# SENSOR_Board.net
KiCad netlist of a schematic drawn in Altium Designer
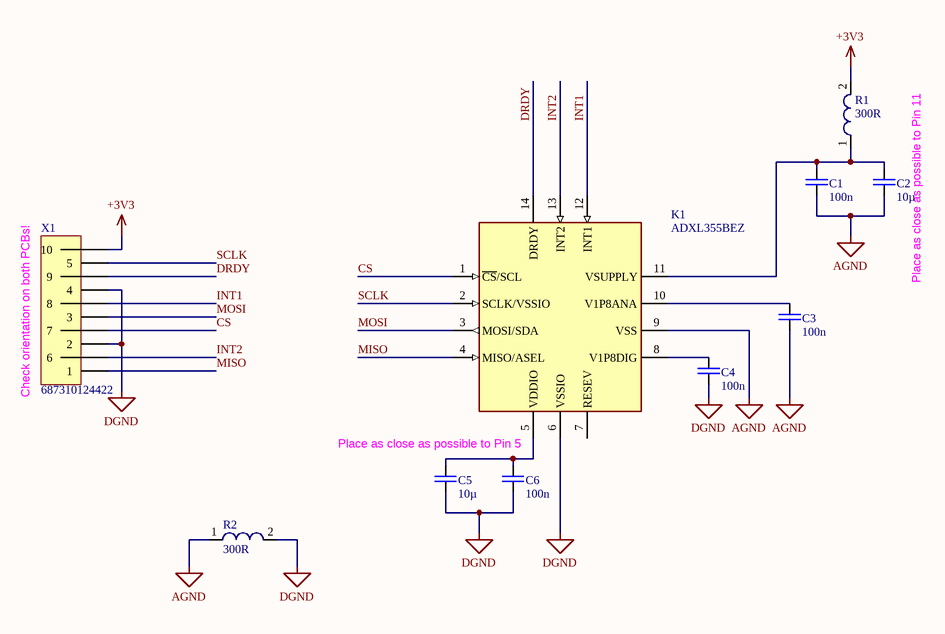
[diagram p0: SENSOR_Board.SchDoc]

(export (version "E")
  (design (tool "Eeschema 10.0.6"))
  (components
    (comp (ref "C1")
      (value "100n")
      (footprint "CAPC1608X08N")
      (description "100n, 0603, X7R, 10%, 50 V")
      (fields (field (name "MANUFACTURER") "Kemet") (field (name "TOLERANCE") "10%"))
      (libsource (lib "Capacitors") (part "C0603C104K5RACTU"))
    )
    (comp (ref "C2")
      (value "10µ")
      (footprint "CAPC2012X14N")
      (description "10µ, 0805, X5R, 10%, 16 V")
      (fields (field (name "MANUFACTURER") "Kemet") (field (name "TOLERANCE") "10%"))
      (libsource (lib "Capacitors") (part "C0805C106K4PACTU"))
    )
    (comp (ref "C3")
      (value "100n")
      (footprint "CAPC1608X08N")
      (description "100n, 0603, X7R, 10%, 50 V")
      (fields (field (name "MANUFACTURER") "Kemet") (field (name "TOLERANCE") "10%"))
      (libsource (lib "Capacitors") (part "C0603C104K5RACTU"))
    )
    (comp (ref "C4")
      (value "100n")
      (footprint "CAPC1608X08N")
      (description "100n, 0603, X7R, 10%, 50 V")
      (fields (field (name "MANUFACTURER") "Kemet") (field (name "TOLERANCE") "10%"))
      (libsource (lib "Capacitors") (part "C0603C104K5RACTU"))
    )
    (comp (ref "C5")
      (value "10µ")
      (footprint "CAPC2012X14N")
      (description "10µ, 0805, X5R, 10%, 16 V")
      (fields (field (name "MANUFACTURER") "Kemet") (field (name "TOLERANCE") "10%"))
      (libsource (lib "Capacitors") (part "C0805C106K4PACTU"))
    )
    (comp (ref "C6")
      (value "100n")
      (footprint "CAPC1608X08N")
      (description "100n, 0603, X7R, 10%, 50 V")
      (fields (field (name "MANUFACTURER") "Kemet") (field (name "TOLERANCE") "10%"))
      (libsource (lib "Capacitors") (part "C0603C104K5RACTU"))
    )
    (comp (ref "K1")
      (value "ADXL355BEZ")
      (footprint "FP-E-14-1-MFG")
      (description "ACCELEROMETER2-4-8GDIGTL14QFN")
      (fields (field (name "MANUFACTURER") "Analog Devices"))
      (libsource (lib "Sensors_MIBE") (part "ADXL355BEZ"))
    )
    (comp (ref "R1")
      (value "300R")
      (footprint "0603 (WE-CBF)")
      (description "300R / 100 MHz, 2 A, 0R15, WE-CBF")
      (fields
        (field (name "MANUFACTURER") "Wurth Electronics")
        (field (name "MANUFACTURER PART NUMBER") "742792641")
      )
      (libsource (lib "Inductors_MIBE") (part "742792641"))
    )
    (comp (ref "R2")
      (value "300R")
      (footprint "0603 (WE-CBF)")
      (description "300R / 100 MHz, 2 A, 0R15, WE-CBF")
      (fields
        (field (name "MANUFACTURER") "Wurth Electronics")
        (field (name "MANUFACTURER PART NUMBER") "742792641")
      )
      (libsource (lib "Inductors_MIBE") (part "742792641"))
    )
    (comp (ref "X1")
      (value "687310124422")
      (footprint "687310124422")
      (description "Ffc / Fpc Board Connector, Vertical, Surface Mount, Receptacle, 10, 0.5 Mm Rohs Compliant: Yes")
      (fields (field (name "MANUFACTURER") "Wurth Electronics"))
      (libsource (lib "Connectors_MIBE") (part "687310124422"))
    )
  )
  (nets
    (net (code "1") (name "+3V3") (class "Default")
      (node (ref "R1") (pin "2") (pinfunction "2_2") (pintype "passive"))
      (node (ref "X1") (pin "10") (pinfunction "10_10") (pintype "passive"))
    )
    (net (code "2") (name "/CS") (class "Default")
      (node (ref "K1") (pin "1") (pinfunction "~{CS}/SCL_1") (pintype "input"))
      (node (ref "X1") (pin "7") (pinfunction "7_7") (pintype "passive"))
    )
    (net (code "3") (name "/DRDY") (class "Default")
      (node (ref "K1") (pin "14") (pinfunction "DRDY_14") (pintype "passive"))
      (node (ref "X1") (pin "9") (pinfunction "9_9") (pintype "passive"))
    )
    (net (code "4") (name "/INT1") (class "Default")
      (node (ref "K1") (pin "12") (pinfunction "INT1_12") (pintype "input"))
      (node (ref "X1") (pin "8") (pinfunction "8_8") (pintype "passive"))
    )
    (net (code "5") (name "/INT2") (class "Default")
      (node (ref "K1") (pin "13") (pinfunction "INT2_13") (pintype "input"))
      (node (ref "X1") (pin "6") (pinfunction "6_6") (pintype "passive"))
    )
    (net (code "6") (name "/MISO") (class "Default")
      (node (ref "K1") (pin "4") (pinfunction "MISO/ASEL_4") (pintype "input"))
      (node (ref "X1") (pin "1") (pinfunction "1_1") (pintype "passive"))
    )
    (net (code "7") (name "/MOSI") (class "Default")
      (node (ref "K1") (pin "3") (pinfunction "MOSI/SDA_3") (pintype "output"))
      (node (ref "X1") (pin "3") (pinfunction "3_3") (pintype "passive"))
    )
    (net (code "8") (name "/SCLK") (class "Default")
      (node (ref "K1") (pin "2") (pinfunction "SCLK/VSSIO_2") (pintype "input"))
      (node (ref "X1") (pin "5") (pinfunction "5_5") (pintype "passive"))
    )
    (net (code "9") (name "AGND") (class "Default")
      (node (ref "C1") (pin "2") (pinfunction "2_2") (pintype "passive"))
      (node (ref "C2") (pin "2") (pinfunction "2_2") (pintype "passive"))
      (node (ref "C3") (pin "2") (pinfunction "2_2") (pintype "passive"))
      (node (ref "K1") (pin "9") (pinfunction "VSS_9") (pintype "power_in"))
      (node (ref "R2") (pin "1") (pinfunction "1_1") (pintype "passive"))
    )
    (net (code "10") (name "DGND") (class "Default")
      (node (ref "C4") (pin "2") (pinfunction "2_2") (pintype "passive"))
      (node (ref "C5") (pin "2") (pinfunction "2_2") (pintype "passive"))
      (node (ref "C6") (pin "2") (pinfunction "2_2") (pintype "passive"))
      (node (ref "K1") (pin "6") (pinfunction "VSSIO_6") (pintype "power_in"))
      (node (ref "R2") (pin "2") (pinfunction "2_2") (pintype "passive"))
      (node (ref "X1") (pin "2") (pinfunction "2_2") (pintype "passive"))
      (node (ref "X1") (pin "4") (pinfunction "4_4") (pintype "passive"))
    )
    (net (code "11") (name "Net-(K1-V1P8ANA)") (class "Default")
      (node (ref "C3") (pin "1") (pinfunction "1_1") (pintype "passive"))
      (node (ref "K1") (pin "10") (pinfunction "V1P8ANA_10") (pintype "power_in"))
    )
    (net (code "12") (name "Net-(K1-V1P8DIG)") (class "Default")
      (node (ref "C4") (pin "1") (pinfunction "1_1") (pintype "passive"))
      (node (ref "K1") (pin "8") (pinfunction "V1P8DIG_8") (pintype "power_in"))
    )
    (net (code "13") (name "Net-(K1-VDDIO)") (class "Default")
      (node (ref "C5") (pin "1") (pinfunction "1_1") (pintype "passive"))
      (node (ref "C6") (pin "1") (pinfunction "1_1") (pintype "passive"))
      (node (ref "K1") (pin "5") (pinfunction "VDDIO_5") (pintype "power_in"))
    )
    (net (code "14") (name "Net-(K1-VSUPPLY)") (class "Default")
      (node (ref "C1") (pin "1") (pinfunction "1_1") (pintype "passive"))
      (node (ref "C2") (pin "1") (pinfunction "1_1") (pintype "passive"))
      (node (ref "K1") (pin "11") (pinfunction "VSUPPLY_11") (pintype "power_in"))
      (node (ref "R1") (pin "1") (pinfunction "1_1") (pintype "passive"))
    )
    (net (code "15") (name "unconnected-(K1-RESEV-Pad7)") (class "Default")
      (node (ref "K1") (pin "7") (pinfunction "RESEV_7") (pintype "passive"))
    )
  )
)
